# synth-zodiac-gemini-envelope.net
KiCad netlist of a schematic drawn in EAGLE
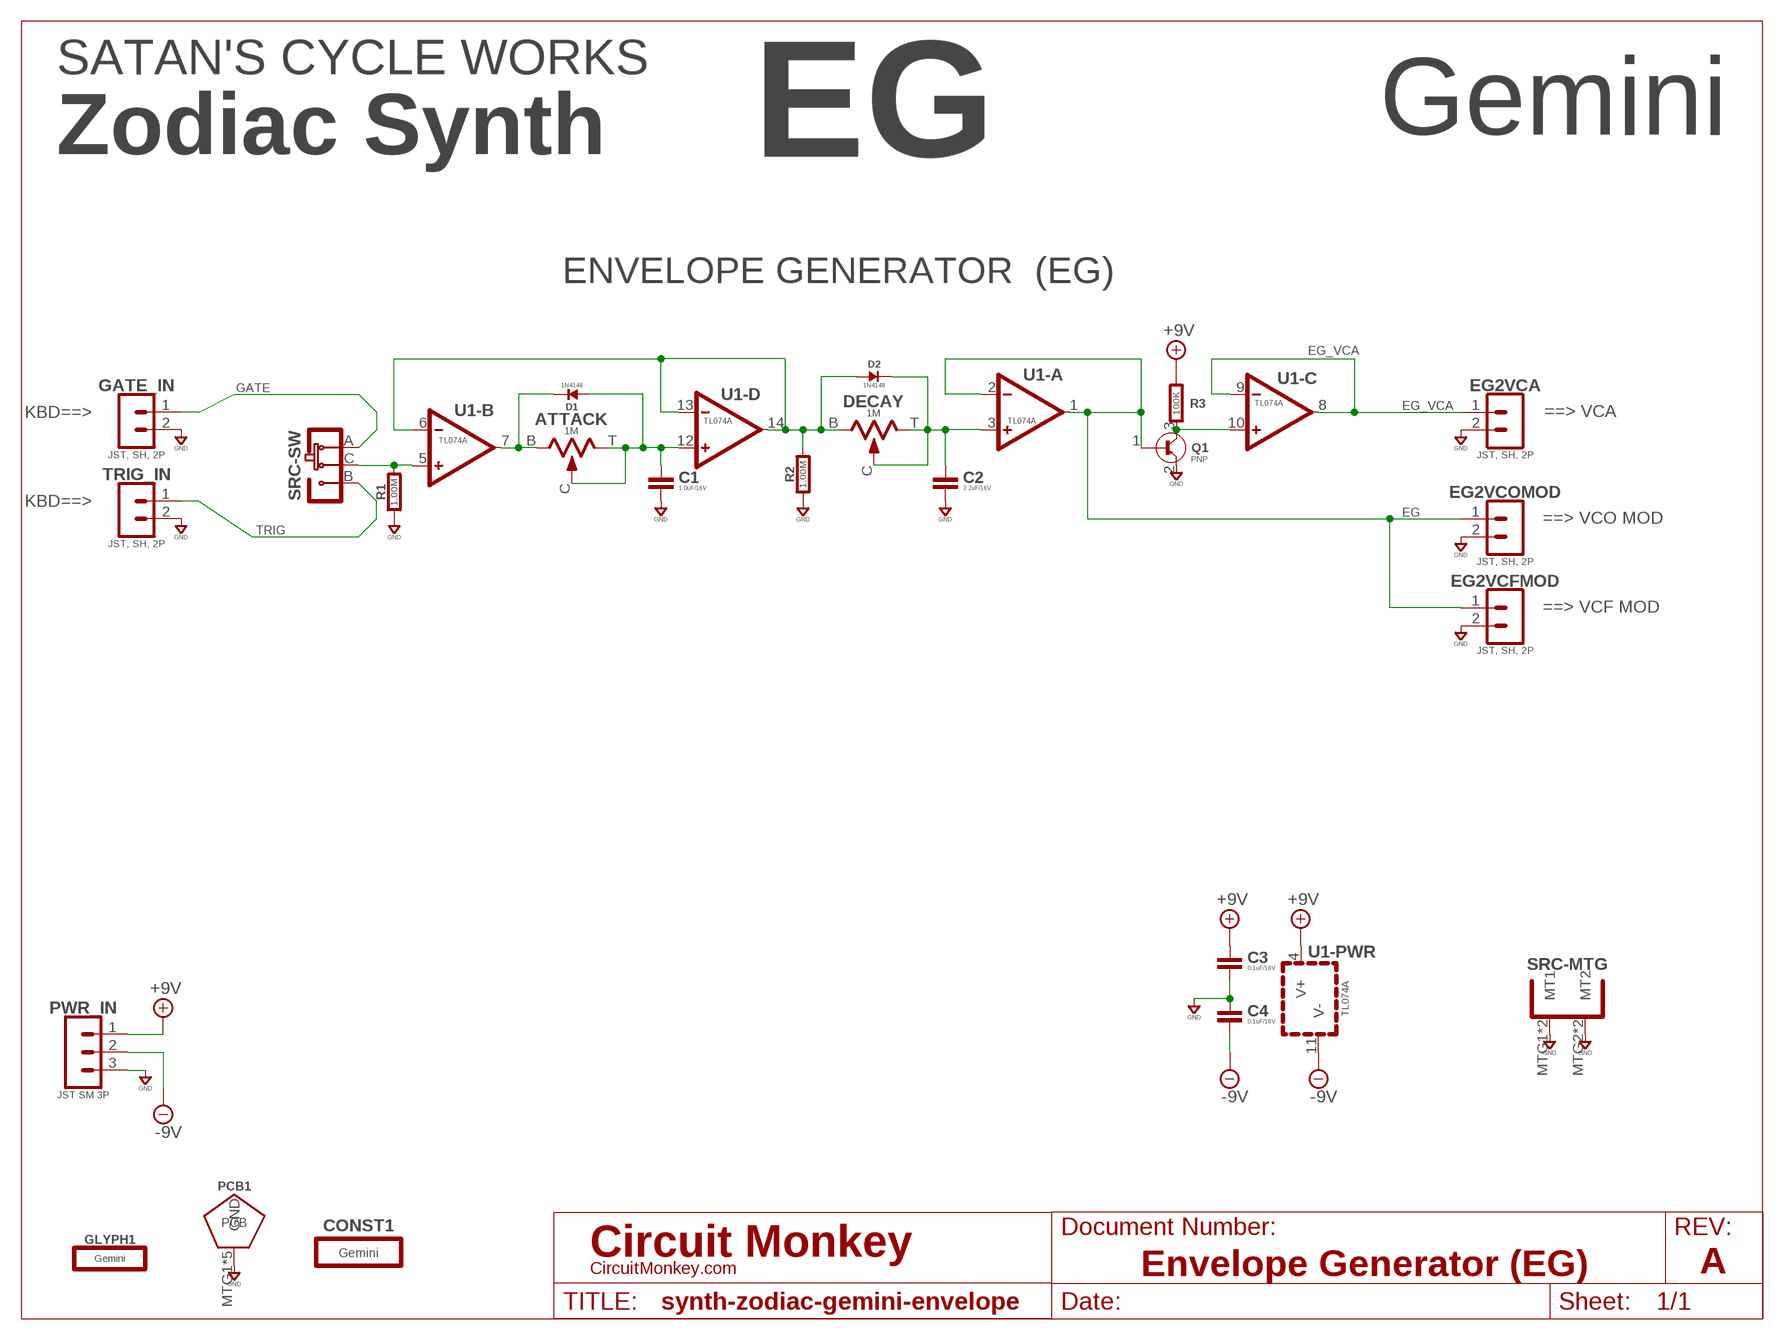
[diagram p0: schematic, sheet 1]

(export (version "E")
  (design (tool "Eeschema 10.0.6"))
  (components
    (comp (ref "ATTACK")
      (value "1M")
      (footprint "eagle-import:POT-RV9110")
      (fields (field (name "MFR") "Tayda") (field (name "MPN") "RV9110NO-OS15A00"))
      (libsource (lib "eagle-import") (part "TRIMPOT9MM_PCB_SHAFT"))
    )
    (comp (ref "C1")
      (value "1.0uF/16V")
      (footprint "eagle-import:0603-CAP")
      (libsource (lib "eagle-import") (part "CAPACITOR0603"))
    )
    (comp (ref "C2")
      (value "2.2uF/16V")
      (footprint "eagle-import:0603-CAP")
      (libsource (lib "eagle-import") (part "CAPACITOR0603"))
    )
    (comp (ref "C3")
      (value "0.1uF/16V")
      (footprint "eagle-import:0603-CAP")
      (libsource (lib "eagle-import") (part "CAPACITOR0603"))
    )
    (comp (ref "C4")
      (value "0.1uF/16V")
      (footprint "eagle-import:0603-CAP")
      (libsource (lib "eagle-import") (part "CAPACITOR0603"))
    )
    (comp (ref "CONST1")
      (value "Gemini")
      (footprint "eagle-import:GEMINI-CONST")
      (libsource (lib "eagle-import") (part "CONSTELLATION-GEMINI"))
    )
    (comp (ref "D1")
      (value "1N4148")
      (footprint "eagle-import:SOD-123")
      (fields (field (name "MPN") "1N4148W"))
      (libsource (lib "eagle-import") (part "DIODE-1N4148"))
    )
    (comp (ref "D2")
      (value "1N4148")
      (footprint "eagle-import:SOD-123")
      (fields (field (name "MPN") "1N4148W"))
      (libsource (lib "eagle-import") (part "DIODE-1N4148"))
    )
    (comp (ref "DECAY")
      (value "1M")
      (footprint "eagle-import:POT-RV9110")
      (fields (field (name "MFR") "Tayda") (field (name "MPN") "RV9110NO-OS15A00"))
      (libsource (lib "eagle-import") (part "TRIMPOT9MM_PCB_SHAFT"))
    )
    (comp (ref "EG2VCA")
      (value "JST, SH, 2P")
      (footprint "eagle-import:BM02B-SRSS-TB")
      (fields (field (name "MFR") "JST") (field (name "MPN") "BMB02B-SRSS-TB"))
      (libsource (lib "eagle-import") (part "02P-SM-VT-SMT"))
    )
    (comp (ref "EG2VCFMOD")
      (value "JST, SH, 2P")
      (footprint "eagle-import:BM02B-SRSS-TB")
      (fields (field (name "MFR") "JST") (field (name "MPN") "BMB02B-SRSS-TB"))
      (libsource (lib "eagle-import") (part "02P-SM-VT-SMT"))
    )
    (comp (ref "EG2VCOMOD")
      (value "JST, SH, 2P")
      (footprint "eagle-import:BM02B-SRSS-TB")
      (fields (field (name "MFR") "JST") (field (name "MPN") "BMB02B-SRSS-TB"))
      (libsource (lib "eagle-import") (part "02P-SM-VT-SMT"))
    )
    (comp (ref "GATE_IN")
      (value "JST, SH, 2P")
      (footprint "eagle-import:BM02B-SRSS-TB")
      (fields (field (name "MFR") "JST") (field (name "MPN") "BMB02B-SRSS-TB"))
      (libsource (lib "eagle-import") (part "02P-SM-VT-SMT"))
    )
    (comp (ref "GLYPH1")
      (value "Gemini")
      (footprint "eagle-import:GEMINI-GLYPH")
      (libsource (lib "eagle-import") (part "GLYPH-GEMINI"))
    )
    (comp (ref "PCB1")
      (value "PCB FAB")
      (footprint "eagle-import:PENTAGON-40MM-RAD")
      (libsource (lib "eagle-import") (part "PENTAGON-40R"))
    )
    (comp (ref "PWR_IN")
      (value "JST SM 3P")
      (footprint "eagle-import:BM03B-SRSS-TB")
      (fields (field (name "MFR") "JST") (field (name "MPN") "BM03B-SRSS-TB"))
      (libsource (lib "eagle-import") (part "03P-SM-VT-SMT"))
    )
    (comp (ref "Q1")
      (value "PNP")
      (footprint "eagle-import:SOT-23")
      (fields (field (name "MFR") "On Semiconductor") (field (name "MPN") "BC856"))
      (libsource (lib "eagle-import") (part "PNP-BC856"))
    )
    (comp (ref "R1")
      (value "1.00M")
      (footprint "eagle-import:0603-RES")
      (libsource (lib "eagle-import") (part "RESISTOR0603"))
    )
    (comp (ref "R2")
      (value "1.00M")
      (footprint "eagle-import:0603-RES")
      (libsource (lib "eagle-import") (part "RESISTOR0603"))
    )
    (comp (ref "R3")
      (value "100K")
      (footprint "eagle-import:0603-RES")
      (libsource (lib "eagle-import") (part "RESISTOR0603"))
    )
    (comp (ref "SRC")
      (value "SLIDE-SPDT-MNTSS-12-F45-TH-PCB-2")
      (footprint "eagle-import:SS-12-F45-PNL-SMT-2")
      (fields (field (name "MFR") "Tayda") (field (name "MPN") "A-659/A-5111/A-5104"))
      (libsource (lib "eagle-import") (part "SLIDE-SPDT-MNTSS-12-F45-TH-PCB-2"))
    )
    (comp (ref "TRIG_IN")
      (value "JST, SH, 2P")
      (footprint "eagle-import:BM02B-SRSS-TB")
      (fields (field (name "MFR") "JST") (field (name "MPN") "BMB02B-SRSS-TB"))
      (libsource (lib "eagle-import") (part "02P-SM-VT-SMT"))
    )
    (comp (ref "U1")
      (value "TL074A")
      (footprint "eagle-import:SOP14")
      (fields (field (name "MFR") "ST") (field (name "MPN") "TL074ACDT"))
      (libsource (lib "eagle-import") (part "QUADTL074A-SOIC"))
    )
  )
  (nets
    (net (code "1") (name "+9V") (class "Default")
      (node (ref "C3") (pin "1") (pinfunction "1_1") (pintype "passive"))
      (node (ref "PWR_IN") (pin "1") (pinfunction "1_1") (pintype "passive"))
      (node (ref "R3") (pin "2") (pinfunction "2_2") (pintype "passive"))
      (node (ref "U1") (pin "4") (pinfunction "V+_4") (pintype "power_in"))
    )
    (net (code "2") (name "-9V") (class "Default")
      (node (ref "C4") (pin "2") (pinfunction "2_2") (pintype "passive"))
      (node (ref "PWR_IN") (pin "2") (pinfunction "2_2") (pintype "passive"))
      (node (ref "U1") (pin "11") (pinfunction "V-_11") (pintype "power_in"))
    )
    (net (code "3") (name "/EG") (class "Default")
      (node (ref "EG2VCFMOD") (pin "1") (pinfunction "1_1") (pintype "passive"))
      (node (ref "EG2VCOMOD") (pin "1") (pinfunction "1_1") (pintype "passive"))
      (node (ref "Q1") (pin "1") (pinfunction "BASE_1") (pintype "bidirectional"))
      (node (ref "U1") (pin "1") (pinfunction "OUT_1") (pintype "output"))
      (node (ref "U1") (pin "2") (pinfunction "-_2") (pintype "input"))
    )
    (net (code "4") (name "/EG_VCA") (class "Default")
      (node (ref "EG2VCA") (pin "1") (pinfunction "1_1") (pintype "passive"))
      (node (ref "U1") (pin "8") (pinfunction "OUT_8") (pintype "output"))
      (node (ref "U1") (pin "9") (pinfunction "-_9") (pintype "input"))
    )
    (net (code "5") (name "/GATE") (class "Default")
      (node (ref "GATE_IN") (pin "1") (pinfunction "1_1") (pintype "passive"))
      (node (ref "SRC") (pin "A") (pinfunction "A_A") (pintype "bidirectional"))
    )
    (net (code "6") (name "/TRIG") (class "Default")
      (node (ref "SRC") (pin "B") (pinfunction "B_B") (pintype "bidirectional"))
      (node (ref "TRIG_IN") (pin "1") (pinfunction "1_1") (pintype "passive"))
    )
    (net (code "7") (name "GND") (class "Default")
      (node (ref "C1") (pin "2") (pinfunction "2_2") (pintype "passive"))
      (node (ref "C2") (pin "2") (pinfunction "2_2") (pintype "passive"))
      (node (ref "C3") (pin "2") (pinfunction "2_2") (pintype "passive"))
      (node (ref "C4") (pin "1") (pinfunction "1_1") (pintype "passive"))
      (node (ref "EG2VCA") (pin "2") (pinfunction "2_2") (pintype "passive"))
      (node (ref "EG2VCFMOD") (pin "2") (pinfunction "2_2") (pintype "passive"))
      (node (ref "EG2VCOMOD") (pin "2") (pinfunction "2_2") (pintype "passive"))
      (node (ref "GATE_IN") (pin "2") (pinfunction "2_2") (pintype "passive"))
      (node (ref "PCB1") (pin "MTG1") (pinfunction "GND_MTG1") (pintype "bidirectional"))
      (node (ref "PCB1") (pin "MTG2") (pinfunction "GND_MTG2") (pintype "bidirectional"))
      (node (ref "PCB1") (pin "MTG3") (pinfunction "GND_MTG3") (pintype "bidirectional"))
      (node (ref "PCB1") (pin "MTG4") (pinfunction "GND_MTG4") (pintype "bidirectional"))
      (node (ref "PCB1") (pin "MTG5") (pinfunction "GND_MTG5") (pintype "bidirectional"))
      (node (ref "PWR_IN") (pin "3") (pinfunction "3_3") (pintype "passive"))
      (node (ref "Q1") (pin "2") (pinfunction "EMITTER_2") (pintype "bidirectional"))
      (node (ref "R1") (pin "1") (pinfunction "1_1") (pintype "passive"))
      (node (ref "R2") (pin "1") (pinfunction "1_1") (pintype "passive"))
      (node (ref "SRC") (pin "MTG1") (pinfunction "MT1_MTG1") (pintype "bidirectional"))
      (node (ref "SRC") (pin "MTG2") (pinfunction "MT2_MTG2") (pintype "bidirectional"))
      (node (ref "SRC") (pin "MTG3") (pinfunction "MT1_MTG3") (pintype "bidirectional"))
      (node (ref "SRC") (pin "MTG4") (pinfunction "MT2_MTG4") (pintype "bidirectional"))
      (node (ref "TRIG_IN") (pin "2") (pinfunction "2_2") (pintype "passive"))
    )
    (net (code "8") (name "Net-(ATTACK-1)") (class "Default")
      (node (ref "ATTACK") (pin "B") (pinfunction "1_B") (pintype "passive"))
      (node (ref "D1") (pin "K") (pinfunction "K_K") (pintype "passive"))
      (node (ref "U1") (pin "7") (pinfunction "OUT_7") (pintype "output"))
    )
    (net (code "9") (name "Net-(ATTACK-2)") (class "Default")
      (node (ref "ATTACK") (pin "C") (pinfunction "2_C") (pintype "passive"))
      (node (ref "ATTACK") (pin "T") (pinfunction "3_T") (pintype "passive"))
      (node (ref "C1") (pin "1") (pinfunction "1_1") (pintype "passive"))
      (node (ref "D1") (pin "A") (pinfunction "A_A") (pintype "passive"))
      (node (ref "U1") (pin "12") (pinfunction "+_12") (pintype "input"))
    )
    (net (code "10") (name "Net-(DECAY-1)") (class "Default")
      (node (ref "D2") (pin "A") (pinfunction "A_A") (pintype "passive"))
      (node (ref "DECAY") (pin "B") (pinfunction "1_B") (pintype "passive"))
      (node (ref "R2") (pin "2") (pinfunction "2_2") (pintype "passive"))
      (node (ref "U1") (pin "13") (pinfunction "-_13") (pintype "input"))
      (node (ref "U1") (pin "14") (pinfunction "OUT_14") (pintype "output"))
      (node (ref "U1") (pin "6") (pinfunction "-_6") (pintype "input"))
    )
    (net (code "11") (name "Net-(DECAY-2)") (class "Default")
      (node (ref "C2") (pin "1") (pinfunction "1_1") (pintype "passive"))
      (node (ref "D2") (pin "K") (pinfunction "K_K") (pintype "passive"))
      (node (ref "DECAY") (pin "C") (pinfunction "2_C") (pintype "passive"))
      (node (ref "DECAY") (pin "T") (pinfunction "3_T") (pintype "passive"))
      (node (ref "U1") (pin "3") (pinfunction "+_3") (pintype "input"))
    )
    (net (code "12") (name "Net-(Q1-COLLECTOR)") (class "Default")
      (node (ref "Q1") (pin "3") (pinfunction "COLLECTOR_3") (pintype "bidirectional"))
      (node (ref "R3") (pin "1") (pinfunction "1_1") (pintype "passive"))
      (node (ref "U1") (pin "10") (pinfunction "+_10") (pintype "input"))
    )
    (net (code "13") (name "Net-(U1B-+)") (class "Default")
      (node (ref "R1") (pin "2") (pinfunction "2_2") (pintype "passive"))
      (node (ref "SRC") (pin "C") (pinfunction "C_C") (pintype "bidirectional"))
      (node (ref "U1") (pin "5") (pinfunction "+_5") (pintype "input"))
    )
  )
)
